# WBoard.net
KiCad netlist of a schematic drawn in Altium Designer
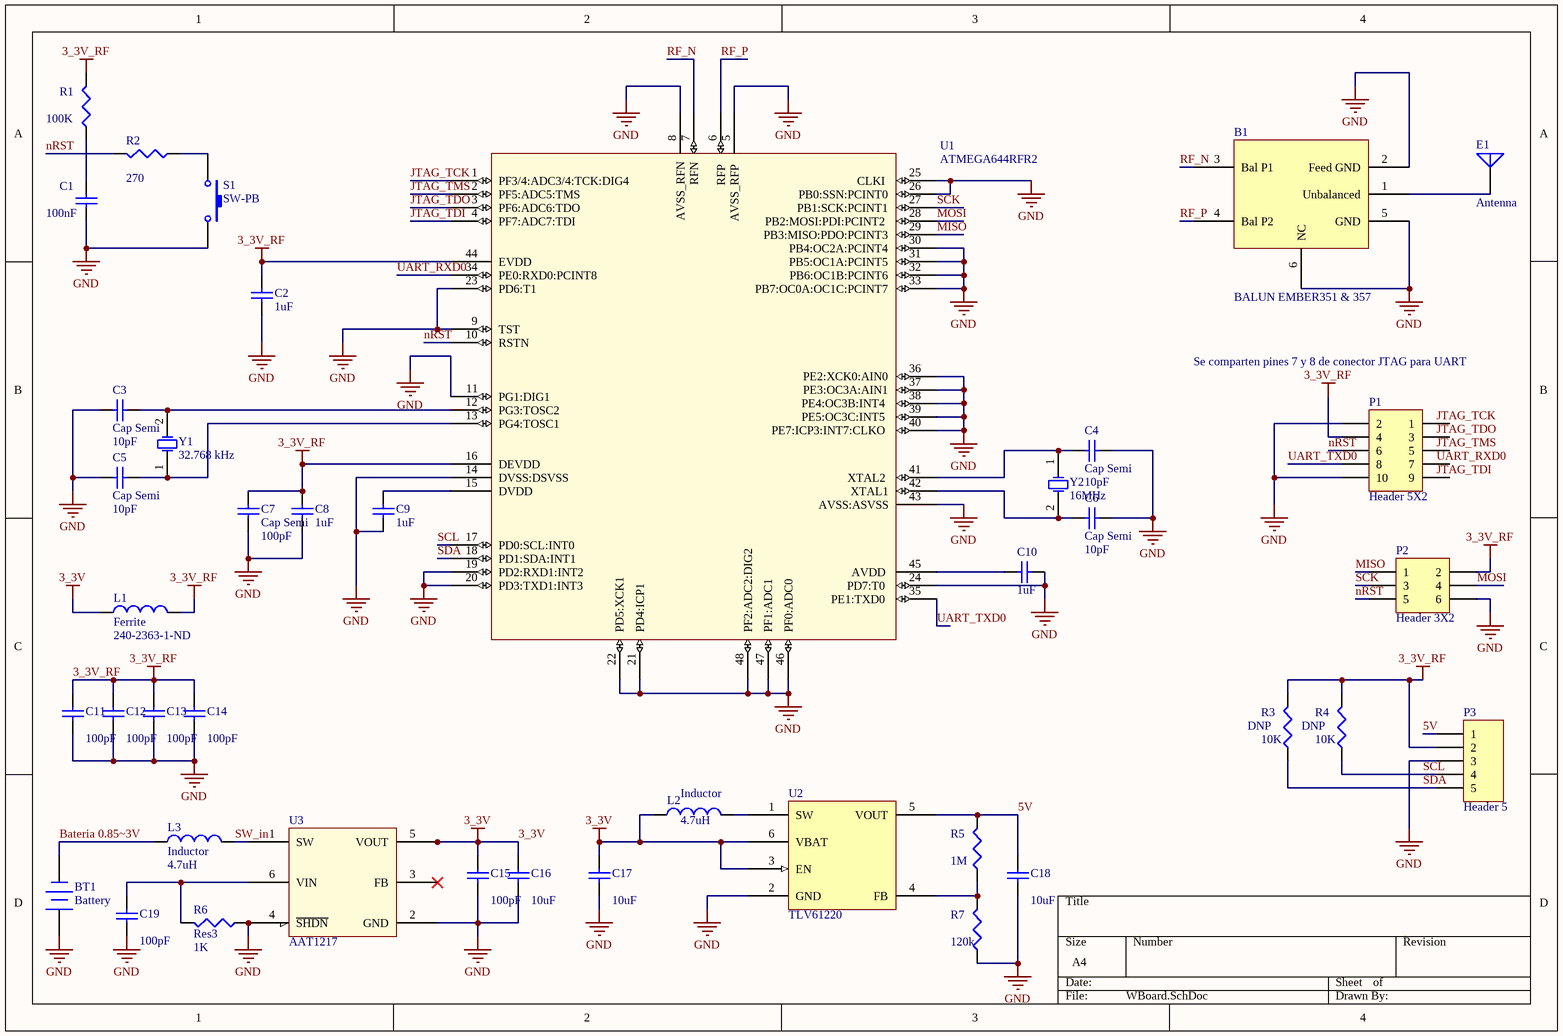
[diagram p0: WBoard.SchDoc]

(export (version "E")
  (design (tool "Eeschema 10.0.6"))
  (components
    (comp (ref "B1")
      (value "BALUN EMBER351 & 357")
      (libsource (lib "sch_comp") (part "BALUN EMBER351 & 357"))
    )
    (comp (ref "BT1")
      (value "Battery")
      (footprint "BAT-2")
      (description "Multicell Battery")
      (fields (field (name "PUBLISHER") "Altium Limited"))
      (libsource (lib "Miscellaneous Devices") (part "Battery"))
    )
    (comp (ref "C1")
      (value "100nF")
      (footprint "C1206")
      (description "Capacitor (Semiconductor SIM Model)")
      (fields (field (name "Comment") "Cap Semi") (field (name "PUBLISHER") "Altium Limited"))
      (libsource (lib "Miscellaneous Devices") (part "Cap Semi"))
    )
    (comp (ref "C2")
      (value "1uF")
      (footprint "C1206")
      (description "Capacitor (Semiconductor SIM Model)")
      (fields (field (name "Comment") "Cap Semi") (field (name "PUBLISHER") "Altium Limited"))
      (libsource (lib "Miscellaneous Devices") (part "Cap Semi"))
    )
    (comp (ref "C3")
      (value "Cap Semi")
      (footprint "1608[0603]")
      (description "Capacitor (Semiconductor SIM Model)")
      (fields (field (name "ALTIUM_VALUE") "10pF") (field (name "PUBLISHER") "Altium Limited"))
      (libsource (lib "Miscellaneous Devices") (part "Cap Semi"))
    )
    (comp (ref "C4")
      (value "Cap Semi")
      (footprint "1608[0603]")
      (description "Capacitor (Semiconductor SIM Model)")
      (fields (field (name "ALTIUM_VALUE") "10pF") (field (name "PUBLISHER") "Altium Limited"))
      (libsource (lib "Miscellaneous Devices") (part "Cap Semi"))
    )
    (comp (ref "C5")
      (value "Cap Semi")
      (footprint "1608[0603]")
      (description "Capacitor (Semiconductor SIM Model)")
      (fields (field (name "ALTIUM_VALUE") "10pF") (field (name "PUBLISHER") "Altium Limited"))
      (libsource (lib "Miscellaneous Devices") (part "Cap Semi"))
    )
    (comp (ref "C6")
      (value "Cap Semi")
      (footprint "1608[0603]")
      (description "Capacitor (Semiconductor SIM Model)")
      (fields (field (name "ALTIUM_VALUE") "10pF") (field (name "PUBLISHER") "Altium Limited"))
      (libsource (lib "Miscellaneous Devices") (part "Cap Semi"))
    )
    (comp (ref "C7")
      (value "Cap Semi")
      (footprint "1608[0603]")
      (description "Capacitor (Semiconductor SIM Model)")
      (fields (field (name "ALTIUM_VALUE") "100pF") (field (name "PUBLISHER") "Altium Limited"))
      (libsource (lib "Miscellaneous Devices") (part "Cap Semi"))
    )
    (comp (ref "C8")
      (value "1uF")
      (footprint "C1206")
      (description "Capacitor (Semiconductor SIM Model)")
      (fields (field (name "Comment") "Cap Semi") (field (name "PUBLISHER") "Altium Limited"))
      (libsource (lib "Miscellaneous Devices") (part "Cap Semi"))
    )
    (comp (ref "C9")
      (value "1uF")
      (footprint "C1206")
      (description "Capacitor (Semiconductor SIM Model)")
      (fields (field (name "Comment") "Cap Semi") (field (name "PUBLISHER") "Altium Limited"))
      (libsource (lib "Miscellaneous Devices") (part "Cap Semi"))
    )
    (comp (ref "C10")
      (value "1uF")
      (footprint "C1206")
      (description "Capacitor (Semiconductor SIM Model)")
      (fields (field (name "Comment") "Cap Semi") (field (name "PUBLISHER") "Altium Limited"))
      (libsource (lib "Miscellaneous Devices") (part "Cap Semi"))
    )
    (comp (ref "C11")
      (value "100pF")
      (footprint "1608[0603]")
      (description "Capacitor (Semiconductor SIM Model)")
      (fields (field (name "Comment") "Cap Semi") (field (name "PUBLISHER") "Altium Limited"))
      (libsource (lib "Miscellaneous Devices") (part "Cap Semi"))
    )
    (comp (ref "C12")
      (value "100pF")
      (footprint "1608[0603]")
      (description "Capacitor (Semiconductor SIM Model)")
      (fields (field (name "Comment") "Cap Semi") (field (name "PUBLISHER") "Altium Limited"))
      (libsource (lib "Miscellaneous Devices") (part "Cap Semi"))
    )
    (comp (ref "C13")
      (value "100pF")
      (footprint "1608[0603]")
      (description "Capacitor (Semiconductor SIM Model)")
      (fields (field (name "Comment") "Cap Semi") (field (name "PUBLISHER") "Altium Limited"))
      (libsource (lib "Miscellaneous Devices") (part "Cap Semi"))
    )
    (comp (ref "C14")
      (value "100pF")
      (footprint "1608[0603]")
      (description "Capacitor (Semiconductor SIM Model)")
      (fields (field (name "Comment") "Cap Semi") (field (name "PUBLISHER") "Altium Limited"))
      (libsource (lib "Miscellaneous Devices") (part "Cap Semi"))
    )
    (comp (ref "C15")
      (value "100pF")
      (footprint "1608[0603]")
      (description "Capacitor (Semiconductor SIM Model)")
      (fields (field (name "Comment") "Cap Semi") (field (name "PUBLISHER") "Altium Limited"))
      (libsource (lib "Miscellaneous Devices") (part "Cap Semi"))
    )
    (comp (ref "C16")
      (value "10uF")
      (footprint "1608[0603]")
      (description "Capacitor (Semiconductor SIM Model)")
      (fields (field (name "Comment") "Cap Semi") (field (name "PUBLISHER") "Altium Limited"))
      (libsource (lib "Miscellaneous Devices") (part "Cap Semi"))
    )
    (comp (ref "C17")
      (value "10uF")
      (footprint "1608[0603]")
      (description "Capacitor (Semiconductor SIM Model)")
      (fields (field (name "Comment") "Cap Semi") (field (name "PUBLISHER") "Altium Limited"))
      (libsource (lib "Miscellaneous Devices") (part "Cap Semi"))
    )
    (comp (ref "C18")
      (value "10uF")
      (footprint "1608[0603]")
      (description "Capacitor (Semiconductor SIM Model)")
      (fields (field (name "Comment") "Cap Semi") (field (name "PUBLISHER") "Altium Limited"))
      (libsource (lib "Miscellaneous Devices") (part "Cap Semi"))
    )
    (comp (ref "C19")
      (value "100pF")
      (footprint "1608[0603]")
      (description "Capacitor (Semiconductor SIM Model)")
      (fields (field (name "Comment") "Cap Semi") (field (name "PUBLISHER") "Altium Limited"))
      (libsource (lib "Miscellaneous Devices") (part "Cap Semi"))
    )
    (comp (ref "E1")
      (value "Antenna")
      (footprint "PIN1")
      (description "Generic Antenna")
      (fields (field (name "PUBLISHER") "Altium Limited"))
      (libsource (lib "Miscellaneous Devices") (part "Antenna"))
    )
    (comp (ref "L1")
      (value "Ferrite")
      (footprint "0402-A")
      (description "Inductor")
      (fields (field (name "ALTIUM_VALUE") "240-2363-1-ND") (field (name "PUBLISHER") "Altium Limited"))
      (libsource (lib "Miscellaneous Devices") (part "Inductor"))
    )
    (comp (ref "L2")
      (value "Inductor")
      (footprint "0402-A")
      (fields (field (name "ALTIUM_VALUE") "4.7uH") (field (name "PUBLISHER") "Altium Limited"))
      (libsource (lib "Miscellaneous Devices") (part "Inductor"))
    )
    (comp (ref "L3")
      (value "Inductor")
      (footprint "0402-A")
      (fields (field (name "ALTIUM_VALUE") "4.7uH") (field (name "PUBLISHER") "Altium Limited"))
      (libsource (lib "Miscellaneous Devices") (part "Inductor"))
    )
    (comp (ref "P1")
      (value "Header 5X2")
      (footprint "HDR2X5")
      (description "Header, 5-Pin, Dual row")
      (fields (field (name "PUBLISHER") "Altium Limited"))
      (libsource (lib "Miscellaneous Connectors") (part "Header 5X2"))
    )
    (comp (ref "P2")
      (value "Header 3X2")
      (footprint "HDR2X3")
      (description "Header, 3-Pin, Dual row")
      (fields (field (name "PUBLISHER") "Altium Limited"))
      (libsource (lib "Miscellaneous Connectors") (part "Header 3X2"))
    )
    (comp (ref "P3")
      (value "Header 5")
      (footprint "HDR1X5")
      (description "Header, 5-Pin")
      (fields (field (name "PUBLISHER") "Altium Limited"))
      (libsource (lib "Miscellaneous Connectors") (part "Header 5"))
    )
    (comp (ref "R1")
      (value "100K")
      (footprint "J1-0603")
      (description "Resistor")
      (fields (field (name "Comment") "Res3") (field (name "PUBLISHER") "Altium Limited"))
      (libsource (lib "Miscellaneous Devices") (part "Res3"))
    )
    (comp (ref "R2")
      (value "270")
      (footprint "J1-0603")
      (description "Resistor")
      (fields (field (name "Comment") "Res3") (field (name "PUBLISHER") "Altium Limited"))
      (libsource (lib "Miscellaneous Devices") (part "Res3"))
    )
    (comp (ref "R3")
      (value "DNP")
      (footprint "J1-0603")
      (description "Resistor")
      (fields (field (name "ALTIUM_VALUE") "10K") (field (name "PUBLISHER") "Altium Limited"))
      (libsource (lib "Miscellaneous Devices") (part "Res3"))
    )
    (comp (ref "R4")
      (value "DNP")
      (footprint "J1-0603")
      (description "Resistor")
      (fields (field (name "ALTIUM_VALUE") "10K") (field (name "PUBLISHER") "Altium Limited"))
      (libsource (lib "Miscellaneous Devices") (part "Res3"))
    )
    (comp (ref "R5")
      (value "1M")
      (footprint "J1-0603")
      (description "Resistor")
      (fields (field (name "Comment") "Res3") (field (name "PUBLISHER") "Altium Limited"))
      (libsource (lib "Miscellaneous Devices") (part "Res3"))
    )
    (comp (ref "R6")
      (value "Res3")
      (footprint "J1-0603")
      (description "Resistor")
      (fields (field (name "ALTIUM_VALUE") "1K") (field (name "PUBLISHER") "Altium Limited"))
      (libsource (lib "Miscellaneous Devices") (part "Res3"))
    )
    (comp (ref "R7")
      (value "120k")
      (footprint "J1-0603")
      (description "Resistor")
      (fields (field (name "Comment") "Res3") (field (name "PUBLISHER") "Altium Limited"))
      (libsource (lib "Miscellaneous Devices") (part "Res3"))
    )
    (comp (ref "S1")
      (value "SW-PB")
      (footprint "SPST-2")
      (description "Switch")
      (fields (field (name "PUBLISHER") "Altium Limited"))
      (libsource (lib "Miscellaneous Devices") (part "SW-PB"))
    )
    (comp (ref "U1")
      (value "ATMEGA644RFR2")
      (footprint "QFN50P700X700-48V4M")
      (libsource (lib "sch_comp") (part "ATMEGA644RFR2"))
    )
    (comp (ref "U2")
      (value "TLV61220")
      (footprint "SOT26A-6N")
      (description "LOW INPUT VOLTAGE STEP-UP CONVERTER IN THIN SOT-23 PACKAGE")
      (libsource (lib "sch_comp") (part "TLV61220"))
    )
    (comp (ref "U3") (value "AAT1217") (footprint "SOT26A-6AL") (libsource (lib "sch_comp") (part "AAT1217")))
    (comp (ref "Y1")
      (value "32.768 kHz")
      (footprint "R38")
      (description "Crystal Oscillator")
      (fields (field (name "PUBLISHER") "Altium Limited"))
      (libsource (lib "Miscellaneous Devices") (part "XTAL"))
    )
    (comp (ref "Y2")
      (value "16MHz")
      (footprint "R38")
      (description "Crystal Oscillator")
      (fields (field (name "PUBLISHER") "Altium Limited"))
      (libsource (lib "Miscellaneous Devices") (part "XTAL"))
    )
  )
  (nets
    (net (code "1") (name "/5V") (class "Default")
      (node (ref "C18") (pin "2") (pinfunction "2_2") (pintype "passive"))
      (node (ref "P3") (pin "1") (pinfunction "1_1") (pintype "passive"))
      (node (ref "R5") (pin "2") (pinfunction "2_2") (pintype "passive"))
      (node (ref "U2") (pin "5") (pinfunction "VOUT_5") (pintype "power_in"))
    )
    (net (code "2") (name "/Bateria 0.85~3V") (class "Default")
      (node (ref "BT1") (pin "2") (pinfunction "-_2") (pintype "passive"))
      (node (ref "L3") (pin "1") (pinfunction "1_1") (pintype "passive"))
    )
    (net (code "3") (name "/JTAG_TCK") (class "Default")
      (node (ref "U1") (pin "1") (pinfunction "PF3/4:ADC3/4:TCK:DIG4_1") (pintype "bidirectional"))
    )
    (net (code "4") (name "/JTAG_TDI") (class "Default")
      (node (ref "U1") (pin "4") (pinfunction "PF7:ADC7:TDI_4") (pintype "bidirectional"))
    )
    (net (code "5") (name "/JTAG_TDO") (class "Default")
      (node (ref "U1") (pin "3") (pinfunction "PF6:ADC6:TDO_3") (pintype "bidirectional"))
    )
    (net (code "6") (name "/JTAG_TMS") (class "Default")
      (node (ref "U1") (pin "2") (pinfunction "PF5:ADC5:TMS_2") (pintype "bidirectional"))
    )
    (net (code "7") (name "/MISO") (class "Default")
      (node (ref "P2") (pin "1") (pinfunction "1_1") (pintype "passive"))
      (node (ref "U1") (pin "29") (pinfunction "PB3:MISO:PDO:PCINT3_29") (pintype "bidirectional"))
    )
    (net (code "8") (name "/MOSI") (class "Default")
      (node (ref "P2") (pin "4") (pinfunction "4_4") (pintype "passive"))
      (node (ref "U1") (pin "28") (pinfunction "PB2:MOSI:PDI:PCINT2_28") (pintype "bidirectional"))
    )
    (net (code "9") (name "/RF_N") (class "Default")
      (node (ref "B1") (pin "3") (pinfunction "Bal_P1_3") (pintype "passive"))
      (node (ref "U1") (pin "7") (pinfunction "RFN_7") (pintype "bidirectional"))
    )
    (net (code "10") (name "/RF_P") (class "Default")
      (node (ref "B1") (pin "4") (pinfunction "Bal_P2_4") (pintype "passive"))
      (node (ref "U1") (pin "6") (pinfunction "RFP_6") (pintype "bidirectional"))
    )
    (net (code "11") (name "/SCK") (class "Default")
      (node (ref "P2") (pin "3") (pinfunction "3_3") (pintype "passive"))
      (node (ref "U1") (pin "27") (pinfunction "PB1:SCK:PCINT1_27") (pintype "bidirectional"))
    )
    (net (code "12") (name "/SCL") (class "Default")
      (node (ref "P3") (pin "4") (pinfunction "4_4") (pintype "passive"))
      (node (ref "R4") (pin "1") (pinfunction "1_1") (pintype "passive"))
      (node (ref "U1") (pin "17") (pinfunction "PD0:SCL:INT0_17") (pintype "bidirectional"))
    )
    (net (code "13") (name "/SDA") (class "Default")
      (node (ref "P3") (pin "5") (pinfunction "5_5") (pintype "passive"))
      (node (ref "R3") (pin "1") (pinfunction "1_1") (pintype "passive"))
      (node (ref "U1") (pin "18") (pinfunction "PD1:SDA:INT1_18") (pintype "bidirectional"))
    )
    (net (code "14") (name "/SW_in") (class "Default")
      (node (ref "L3") (pin "2") (pinfunction "2_2") (pintype "passive"))
      (node (ref "U3") (pin "1") (pinfunction "SW_1") (pintype "power_in"))
    )
    (net (code "15") (name "/UART_RXD0") (class "Default")
      (node (ref "U1") (pin "34") (pinfunction "PE0:RXD0:PCINT8_34") (pintype "bidirectional"))
    )
    (net (code "16") (name "/UART_TXD0") (class "Default")
      (node (ref "P1") (pin "8") (pinfunction "8_8") (pintype "passive"))
      (node (ref "U1") (pin "35") (pinfunction "PE1:TXD0_35") (pintype "bidirectional"))
    )
    (net (code "17") (name "/nRST") (class "Default")
      (node (ref "P1") (pin "6") (pinfunction "6_6") (pintype "passive"))
      (node (ref "P2") (pin "5") (pinfunction "5_5") (pintype "passive"))
      (node (ref "R2") (pin "2") (pinfunction "2_2") (pintype "passive"))
      (node (ref "U1") (pin "10") (pinfunction "RSTN_10") (pintype "bidirectional"))
    )
    (net (code "18") (name "3_3V") (class "Default")
      (node (ref "C15") (pin "2") (pinfunction "2_2") (pintype "passive"))
      (node (ref "C16") (pin "2") (pinfunction "2_2") (pintype "passive"))
      (node (ref "C17") (pin "2") (pinfunction "2_2") (pintype "passive"))
      (node (ref "L1") (pin "1") (pinfunction "1_1") (pintype "passive"))
      (node (ref "L2") (pin "1") (pinfunction "1_1") (pintype "passive"))
      (node (ref "U2") (pin "3") (pinfunction "EN_3") (pintype "input"))
      (node (ref "U2") (pin "6") (pinfunction "VBAT_6") (pintype "power_in"))
      (node (ref "U3") (pin "5") (pinfunction "VOUT_5") (pintype "power_in"))
    )
    (net (code "19") (name "3_3V_RF") (class "Default")
      (node (ref "C11") (pin "2") (pinfunction "2_2") (pintype "passive"))
      (node (ref "C12") (pin "2") (pinfunction "2_2") (pintype "passive"))
      (node (ref "C13") (pin "2") (pinfunction "2_2") (pintype "passive"))
      (node (ref "C14") (pin "2") (pinfunction "2_2") (pintype "passive"))
      (node (ref "C2") (pin "1") (pinfunction "1_1") (pintype "passive"))
      (node (ref "C7") (pin "2") (pinfunction "2_2") (pintype "passive"))
      (node (ref "C8") (pin "1") (pinfunction "1_1") (pintype "passive"))
      (node (ref "L1") (pin "2") (pinfunction "2_2") (pintype "passive"))
      (node (ref "P1") (pin "4") (pinfunction "4_4") (pintype "passive"))
      (node (ref "P2") (pin "2") (pinfunction "2_2") (pintype "passive"))
      (node (ref "P3") (pin "2") (pinfunction "2_2") (pintype "passive"))
      (node (ref "R1") (pin "2") (pinfunction "2_2") (pintype "passive"))
      (node (ref "R3") (pin "2") (pinfunction "2_2") (pintype "passive"))
      (node (ref "R4") (pin "2") (pinfunction "2_2") (pintype "passive"))
      (node (ref "U1") (pin "16") (pinfunction "DEVDD_16") (pintype "power_in"))
      (node (ref "U1") (pin "44") (pinfunction "EVDD_44") (pintype "power_in"))
    )
    (net (code "20") (name "GND") (class "Default")
      (node (ref "B1") (pin "2") (pinfunction "Feed_GND_2") (pintype "power_in"))
      (node (ref "B1") (pin "5") (pinfunction "GND_5") (pintype "power_in"))
      (node (ref "B1") (pin "6") (pinfunction "NC_6") (pintype "passive"))
      (node (ref "BT1") (pin "1") (pinfunction "+_1") (pintype "passive"))
      (node (ref "C1") (pin "2") (pinfunction "2_2") (pintype "passive"))
      (node (ref "C10") (pin "2") (pinfunction "2_2") (pintype "passive"))
      (node (ref "C11") (pin "1") (pinfunction "1_1") (pintype "passive"))
      (node (ref "C12") (pin "1") (pinfunction "1_1") (pintype "passive"))
      (node (ref "C13") (pin "1") (pinfunction "1_1") (pintype "passive"))
      (node (ref "C14") (pin "1") (pinfunction "1_1") (pintype "passive"))
      (node (ref "C15") (pin "1") (pinfunction "1_1") (pintype "passive"))
      (node (ref "C16") (pin "1") (pinfunction "1_1") (pintype "passive"))
      (node (ref "C17") (pin "1") (pinfunction "1_1") (pintype "passive"))
      (node (ref "C18") (pin "1") (pinfunction "1_1") (pintype "passive"))
      (node (ref "C19") (pin "1") (pinfunction "1_1") (pintype "passive"))
      (node (ref "C2") (pin "2") (pinfunction "2_2") (pintype "passive"))
      (node (ref "C3") (pin "1") (pinfunction "1_1") (pintype "passive"))
      (node (ref "C4") (pin "1") (pinfunction "1_1") (pintype "passive"))
      (node (ref "C5") (pin "1") (pinfunction "1_1") (pintype "passive"))
      (node (ref "C6") (pin "1") (pinfunction "1_1") (pintype "passive"))
      (node (ref "C7") (pin "1") (pinfunction "1_1") (pintype "passive"))
      (node (ref "C8") (pin "2") (pinfunction "2_2") (pintype "passive"))
      (node (ref "C9") (pin "2") (pinfunction "2_2") (pintype "passive"))
      (node (ref "P1") (pin "10") (pinfunction "10_10") (pintype "passive"))
      (node (ref "P1") (pin "2") (pinfunction "2_2") (pintype "passive"))
      (node (ref "P2") (pin "6") (pinfunction "6_6") (pintype "passive"))
      (node (ref "P3") (pin "3") (pinfunction "3_3") (pintype "passive"))
      (node (ref "R6") (pin "1") (pinfunction "1_1") (pintype "passive"))
      (node (ref "R7") (pin "1") (pinfunction "1_1") (pintype "passive"))
      (node (ref "S1") (pin "2") (pinfunction "2_2") (pintype "passive"))
      (node (ref "U1") (pin "11") (pinfunction "PG1:DIG1_11") (pintype "bidirectional"))
      (node (ref "U1") (pin "14") (pinfunction "DVSS:DSVSS_14") (pintype "power_in"))
      (node (ref "U1") (pin "19") (pinfunction "PD2:RXD1:INT2_19") (pintype "bidirectional"))
      (node (ref "U1") (pin "20") (pinfunction "PD3:TXD1:INT3_20") (pintype "bidirectional"))
      (node (ref "U1") (pin "21") (pinfunction "PD4:ICP1_21") (pintype "bidirectional"))
      (node (ref "U1") (pin "22") (pinfunction "PD5:XCK1_22") (pintype "bidirectional"))
      (node (ref "U1") (pin "23") (pinfunction "PD6:T1_23") (pintype "bidirectional"))
      (node (ref "U1") (pin "24") (pinfunction "PD7:T0_24") (pintype "bidirectional"))
      (node (ref "U1") (pin "25") (pinfunction "CLKI_25") (pintype "bidirectional"))
      (node (ref "U1") (pin "26") (pinfunction "PB0:SSN:PCINT0_26") (pintype "bidirectional"))
      (node (ref "U1") (pin "30") (pinfunction "PB4:OC2A:PCINT4_30") (pintype "bidirectional"))
      (node (ref "U1") (pin "31") (pinfunction "PB5:OC1A:PCINT5_31") (pintype "bidirectional"))
      (node (ref "U1") (pin "32") (pinfunction "PB6:OC1B:PCINT6_32") (pintype "bidirectional"))
      (node (ref "U1") (pin "33") (pinfunction "PB7:OC0A:OC1C:PCINT7_33") (pintype "bidirectional"))
      (node (ref "U1") (pin "36") (pinfunction "PE2:XCK0:AIN0_36") (pintype "bidirectional"))
      (node (ref "U1") (pin "37") (pinfunction "PE3:OC3A:AIN1_37") (pintype "bidirectional"))
      (node (ref "U1") (pin "38") (pinfunction "PE4:OC3B:INT4_38") (pintype "bidirectional"))
      (node (ref "U1") (pin "39") (pinfunction "PE5:OC3C:INT5_39") (pintype "bidirectional"))
      (node (ref "U1") (pin "40") (pinfunction "PE7:ICP3:INT7:CLKO_40") (pintype "bidirectional"))
      (node (ref "U1") (pin "43") (pinfunction "AVSS:ASVSS_43") (pintype "power_in"))
      (node (ref "U1") (pin "46") (pinfunction "PF0:ADC0_46") (pintype "bidirectional"))
      (node (ref "U1") (pin "47") (pinfunction "PF1:ADC1_47") (pintype "bidirectional"))
      (node (ref "U1") (pin "48") (pinfunction "PF2:ADC2:DIG2_48") (pintype "bidirectional"))
      (node (ref "U1") (pin "5") (pinfunction "AVSS_RFP_5") (pintype "power_in"))
      (node (ref "U1") (pin "8") (pinfunction "AVSS_RFN_8") (pintype "power_in"))
      (node (ref "U1") (pin "9") (pinfunction "TST_9") (pintype "bidirectional"))
      (node (ref "U2") (pin "2") (pinfunction "GND_2") (pintype "power_in"))
      (node (ref "U3") (pin "2") (pinfunction "GND_2") (pintype "power_in"))
      (node (ref "U3") (pin "4") (pinfunction "~{SHDN}_4") (pintype "passive"))
    )
    (net (code "21") (name "Net-(B1-Unbalanced)") (class "Default")
      (node (ref "B1") (pin "1") (pinfunction "Unbalanced_1") (pintype "passive"))
      (node (ref "E1") (pin "1") (pinfunction "A_1") (pintype "passive"))
    )
    (net (code "22") (name "Net-(C1-Pad1)") (class "Default")
      (node (ref "C1") (pin "1") (pinfunction "1_1") (pintype "passive"))
      (node (ref "R1") (pin "1") (pinfunction "1_1") (pintype "passive"))
    )
    (net (code "23") (name "Net-(R2-Pad1)") (class "Default")
      (node (ref "R2") (pin "1") (pinfunction "1_1") (pintype "passive"))
      (node (ref "S1") (pin "1") (pinfunction "1_1") (pintype "passive"))
    )
    (net (code "24") (name "Net-(U1-AVDD)") (class "Default")
      (node (ref "C10") (pin "1") (pinfunction "1_1") (pintype "passive"))
      (node (ref "U1") (pin "45") (pinfunction "AVDD_45") (pintype "power_in"))
    )
    (net (code "25") (name "Net-(U1-DVDD)") (class "Default")
      (node (ref "C9") (pin "1") (pinfunction "1_1") (pintype "passive"))
      (node (ref "U1") (pin "15") (pinfunction "DVDD_15") (pintype "power_in"))
    )
    (net (code "26") (name "Net-(U1-PG3:TOSC2)") (class "Default")
      (node (ref "C3") (pin "2") (pinfunction "2_2") (pintype "passive"))
      (node (ref "U1") (pin "12") (pinfunction "PG3:TOSC2_12") (pintype "bidirectional"))
      (node (ref "Y1") (pin "2") (pinfunction "OSC2_2") (pintype "passive"))
    )
    (net (code "27") (name "Net-(U1-PG4:TOSC1)") (class "Default")
      (node (ref "C5") (pin "2") (pinfunction "2_2") (pintype "passive"))
      (node (ref "U1") (pin "13") (pinfunction "PG4:TOSC1_13") (pintype "bidirectional"))
      (node (ref "Y1") (pin "1") (pinfunction "OSC1_1") (pintype "passive"))
    )
    (net (code "28") (name "Net-(U1-XTAL1)") (class "Default")
      (node (ref "C6") (pin "2") (pinfunction "2_2") (pintype "passive"))
      (node (ref "U1") (pin "42") (pinfunction "XTAL1_42") (pintype "bidirectional"))
      (node (ref "Y2") (pin "2") (pinfunction "OSC2_2") (pintype "passive"))
    )
    (net (code "29") (name "Net-(U1-XTAL2)") (class "Default")
      (node (ref "C4") (pin "2") (pinfunction "2_2") (pintype "passive"))
      (node (ref "U1") (pin "41") (pinfunction "XTAL2_41") (pintype "bidirectional"))
      (node (ref "Y2") (pin "1") (pinfunction "OSC1_1") (pintype "passive"))
    )
    (net (code "30") (name "Net-(U2-FB)") (class "Default")
      (node (ref "R5") (pin "1") (pinfunction "1_1") (pintype "passive"))
      (node (ref "R7") (pin "2") (pinfunction "2_2") (pintype "passive"))
      (node (ref "U2") (pin "4") (pinfunction "FB_4") (pintype "passive"))
    )
    (net (code "31") (name "Net-(U2-SW)") (class "Default")
      (node (ref "L2") (pin "2") (pinfunction "2_2") (pintype "passive"))
      (node (ref "U2") (pin "1") (pinfunction "SW_1") (pintype "passive"))
    )
    (net (code "32") (name "Net-(U3-VIN)") (class "Default")
      (node (ref "C19") (pin "2") (pinfunction "2_2") (pintype "passive"))
      (node (ref "R6") (pin "2") (pinfunction "2_2") (pintype "passive"))
      (node (ref "U3") (pin "6") (pinfunction "VIN_6") (pintype "power_in"))
    )
    (net (code "33") (name "unconnected-(P1-Pad1)") (class "Default")
      (node (ref "P1") (pin "1") (pinfunction "1_1") (pintype "passive"))
    )
    (net (code "34") (name "unconnected-(P1-Pad3)") (class "Default")
      (node (ref "P1") (pin "3") (pinfunction "3_3") (pintype "passive"))
    )
    (net (code "35") (name "unconnected-(P1-Pad5)") (class "Default")
      (node (ref "P1") (pin "5") (pinfunction "5_5") (pintype "passive"))
    )
    (net (code "36") (name "unconnected-(P1-Pad7)") (class "Default")
      (node (ref "P1") (pin "7") (pinfunction "7_7") (pintype "passive"))
    )
    (net (code "37") (name "unconnected-(P1-Pad9)") (class "Default")
      (node (ref "P1") (pin "9") (pinfunction "9_9") (pintype "passive"))
    )
    (net (code "38") (name "unconnected-(U3-FB-Pad3)") (class "Default")
      (node (ref "U3") (pin "3") (pinfunction "FB_3") (pintype "passive+no_connect"))
    )
  )
)
